# Threeno_Tx_Rev1B.net
KiCad netlist of a schematic drawn in EAGLE
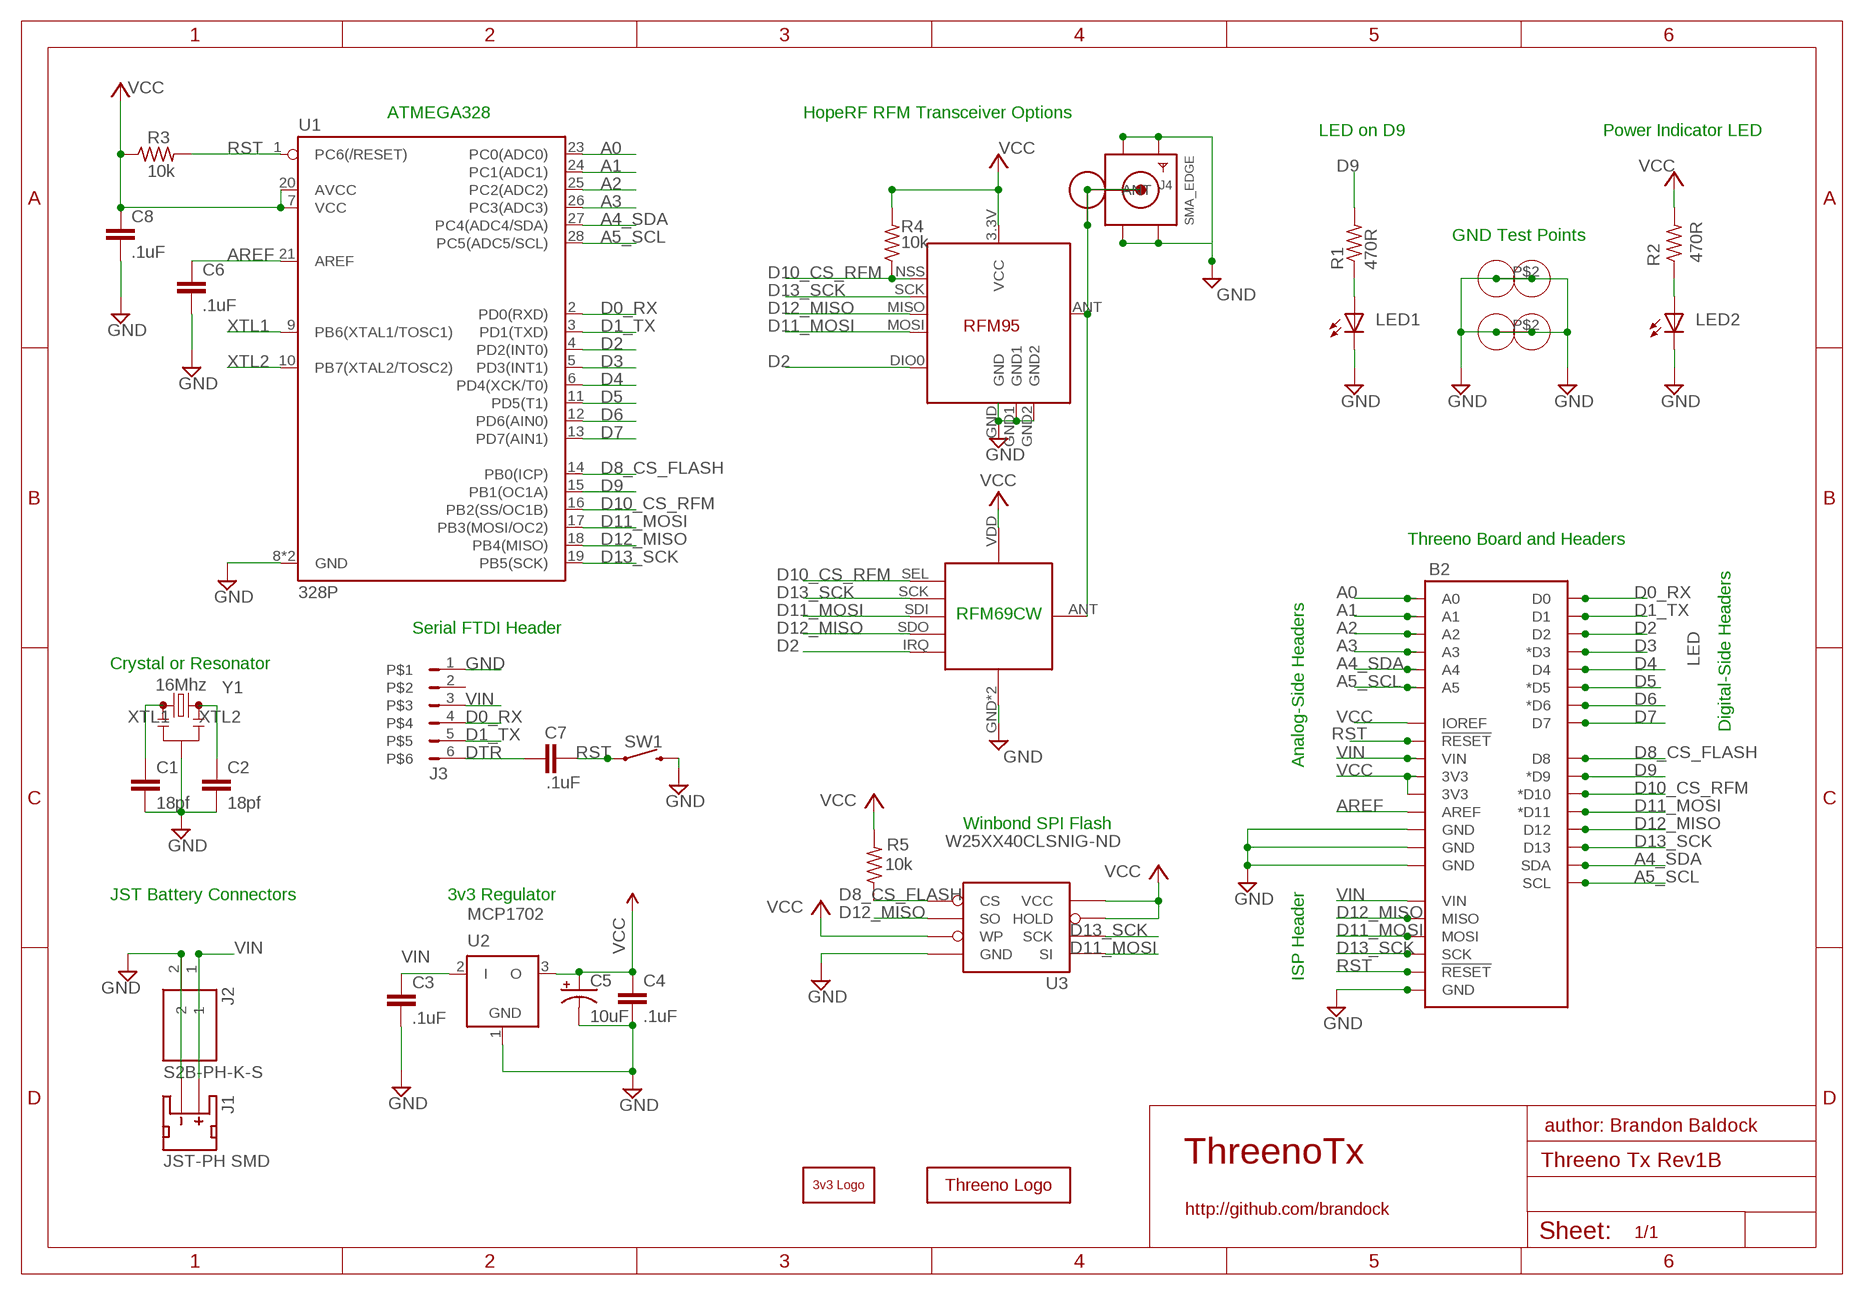
[diagram p0: schematic, sheet 1]

(export (version "E")
  (design (tool "Eeschema 10.0.6"))
  (components
    (comp (ref "B1")
      (value "3VTHREENO_BOTTOM_SILK")
      (footprint "eagle-import:3VTHREENO_BOTTOM_SILK")
      (libsource (lib "eagle-import") (part "3VTHREENO_BOTTOM_SILK"))
    )
    (comp (ref "B2")
      (value "THREENO_TX_BOARD3VTHREENO")
      (footprint "eagle-import:THREENO_TX_BOARD")
      (libsource (lib "eagle-import") (part "THREENO_TX_BOARD3VTHREENO"))
    )
    (comp (ref "B3")
      (value "3VTHREENO_LOGO")
      (footprint "eagle-import:3VTHREENO_LOGO")
      (libsource (lib "eagle-import") (part "3VTHREENO_LOGO"))
    )
    (comp (ref "C1")
      (value "18pf")
      (footprint "eagle-import:C025-024X044-NO-MIDDLE-SILK")
      (libsource (lib "eagle-import") (part "C-EU025-024X044-NO_MIDDLE_SILK"))
    )
    (comp (ref "C2")
      (value "18pf")
      (footprint "eagle-import:C025-024X044-NO-MIDDLE-SILK")
      (libsource (lib "eagle-import") (part "C-EU025-024X044-NO_MIDDLE_SILK"))
    )
    (comp (ref "C3")
      (value ".1uF")
      (footprint "eagle-import:C025-024X044-NO-MIDDLE-SILK")
      (libsource (lib "eagle-import") (part "C-EU025-024X044-NO_MIDDLE_SILK"))
    )
    (comp (ref "C4")
      (value ".1uF")
      (footprint "eagle-import:C025-024X044-NO-MIDDLE-SILK")
      (libsource (lib "eagle-import") (part "C-EU025-024X044-NO_MIDDLE_SILK"))
    )
    (comp (ref "C5")
      (value "10uF")
      (footprint "eagle-import:E1,8-4")
      (libsource (lib "eagle-import") (part "CPOL-USE1.8-4"))
    )
    (comp (ref "C6")
      (value ".1uF")
      (footprint "eagle-import:C025-024X044-NO-MIDDLE-SILK")
      (libsource (lib "eagle-import") (part "C-EU025-024X044-NO_MIDDLE_SILK"))
    )
    (comp (ref "C7")
      (value ".1uF")
      (footprint "eagle-import:C025-024X044-NO-MIDDLE-SILK")
      (libsource (lib "eagle-import") (part "C-EU025-024X044-NO_MIDDLE_SILK"))
    )
    (comp (ref "C8")
      (value ".1uF")
      (footprint "eagle-import:C025-024X044-NO-MIDDLE-SILK")
      (libsource (lib "eagle-import") (part "C-EU025-024X044-NO_MIDDLE_SILK"))
    )
    (comp (ref "J1")
      (value "JST-PH-SMD")
      (footprint "eagle-import:JST-2-SMD")
      (libsource (lib "eagle-import") (part "JST_2MM_MALE"))
    )
    (comp (ref "J2")
      (value "S2B-PH-K-S")
      (footprint "eagle-import:S2BPHKS")
      (libsource (lib "eagle-import") (part "S2B-PH-K-S"))
    )
    (comp (ref "J3")
      (value "FTDI")
      (footprint "eagle-import:FTDI_ROUND_HEADER_SILK")
      (libsource (lib "eagle-import") (part "FTDI"))
    )
    (comp (ref "J4")
      (value "SMA_EDGE")
      (footprint "eagle-import:SMA_EDGELAUNCH")
      (libsource (lib "eagle-import") (part "SMACONNECTOR_EDGE"))
    )
    (comp (ref "J5")
      (value "RFM12B_ANTENNA")
      (footprint "eagle-import:RFM12B-ANTENNA")
      (libsource (lib "eagle-import") (part "RFM12B_ANTENNA"))
    )
    (comp (ref "J6")
      (value "ALLIGATORCLIP-WIRELOOP")
      (footprint "eagle-import:ALLIGATORCLIP-WIRELOOP")
      (libsource (lib "eagle-import") (part "ALLIGATORCLIP-WIRELOOP"))
    )
    (comp (ref "J7")
      (value "ALLIGATORCLIP-WIRELOOP")
      (footprint "eagle-import:ALLIGATORCLIP-WIRELOOP")
      (libsource (lib "eagle-import") (part "ALLIGATORCLIP-WIRELOOP"))
    )
    (comp (ref "LED1")
      (value "LED")
      (footprint "eagle-import:LED3MM-BRANDOCK")
      (libsource (lib "eagle-import") (part "LED-BRANDOCK3MM"))
    )
    (comp (ref "LED2")
      (value "LED")
      (footprint "eagle-import:LED3MM-BRANDOCK")
      (libsource (lib "eagle-import") (part "LED-BRANDOCK3MM"))
    )
    (comp (ref "R1")
      (value "470R")
      (footprint "eagle-import:0204_7")
      (libsource (lib "eagle-import") (part "R-US_0204/7"))
    )
    (comp (ref "R2")
      (value "470R")
      (footprint "eagle-import:0204_7")
      (libsource (lib "eagle-import") (part "R-US_0204/7"))
    )
    (comp (ref "R3")
      (value "10k")
      (footprint "eagle-import:0204_7")
      (libsource (lib "eagle-import") (part "R-US_0204/7"))
    )
    (comp (ref "R4")
      (value "10k")
      (footprint "eagle-import:0204_7")
      (libsource (lib "eagle-import") (part "R-US_0204/7"))
    )
    (comp (ref "R5")
      (value "10k")
      (footprint "eagle-import:0204_7")
      (libsource (lib "eagle-import") (part "R-US_0204/7"))
    )
    (comp (ref "RF1")
      (value "RFM12B_MINPADS")
      (footprint "eagle-import:RFM12B-MINPADS")
      (libsource (lib "eagle-import") (part "RFM12B_MINPADS"))
    )
    (comp (ref "RF2")
      (value "RFM95LONGER")
      (footprint "eagle-import:RFM95_LONGER")
      (libsource (lib "eagle-import") (part "RFM95LONGER"))
    )
    (comp (ref "SW1")
      (value "MOMENTARY-SWITCH-SPST-PTH-6.0MM")
      (footprint "eagle-import:TACTILE_SWITCH_PTH_6.0MM")
      (libsource (lib "eagle-import") (part "MOMENTARY-SWITCH-SPST-PTH-6.0MM"))
    )
    (comp (ref "U1")
      (value "328P")
      (footprint "eagle-import:DIP28-OVALPADS")
      (libsource (lib "eagle-import") (part "ATMEGA328P_PDIP_DIL28"))
    )
    (comp (ref "U2")
      (value "JEELABS_MCP1702Z")
      (footprint "eagle-import:JEELABS_TO92")
      (fields (field (name "LDO") "MCP1702"))
      (libsource (lib "eagle-import") (part "JEELABS_MCP1702Z"))
    )
    (comp (ref "U3")
      (value "AT25F512BJEDEC_3.9MM")
      (footprint "eagle-import:SO08")
      (fields (field (name "FLASH_MEM") "W25XX40CLSNIG-ND"))
      (libsource (lib "eagle-import") (part "AT25F512BJEDEC_3.9MM"))
    )
    (comp (ref "Y1")
      (value "16Mhz")
      (footprint "eagle-import:HC49US-OR-RESONATOR")
      (libsource (lib "eagle-import") (part "CRYSTAL-OR-RESONATOR"))
    )
  )
  (nets
    (net (code "1") (name "/A0") (class "Default")
      (node (ref "B2") (pin "A0") (pinfunction "A0_A0") (pintype "bidirectional"))
      (node (ref "U1") (pin "23") (pinfunction "PC0(ADC0)_23") (pintype "bidirectional"))
    )
    (net (code "2") (name "/A1") (class "Default")
      (node (ref "B2") (pin "A1") (pinfunction "A1_A1") (pintype "bidirectional"))
      (node (ref "U1") (pin "24") (pinfunction "PC1(ADC1)_24") (pintype "bidirectional"))
    )
    (net (code "3") (name "/A2") (class "Default")
      (node (ref "B2") (pin "A2") (pinfunction "A2_A2") (pintype "bidirectional"))
      (node (ref "U1") (pin "25") (pinfunction "PC2(ADC2)_25") (pintype "bidirectional"))
    )
    (net (code "4") (name "/A3") (class "Default")
      (node (ref "B2") (pin "A3") (pinfunction "A3_A3") (pintype "bidirectional"))
      (node (ref "U1") (pin "26") (pinfunction "PC3(ADC3)_26") (pintype "bidirectional"))
    )
    (net (code "5") (name "/A4_SDA") (class "Default")
      (node (ref "B2") (pin "A4") (pinfunction "A4_A4") (pintype "bidirectional"))
      (node (ref "B2") (pin "SDA") (pinfunction "SDA_SDA") (pintype "bidirectional"))
      (node (ref "U1") (pin "27") (pinfunction "PC4(ADC4/SDA)_27") (pintype "bidirectional"))
    )
    (net (code "6") (name "/A5_SCL") (class "Default")
      (node (ref "B2") (pin "A5") (pinfunction "A5_A5") (pintype "bidirectional"))
      (node (ref "B2") (pin "SCL") (pinfunction "SCL_SCL") (pintype "bidirectional"))
      (node (ref "U1") (pin "28") (pinfunction "PC5(ADC5/SCL)_28") (pintype "bidirectional"))
    )
    (net (code "7") (name "/AREF") (class "Default")
      (node (ref "B2") (pin "AREF") (pinfunction "AREF_AREF") (pintype "bidirectional"))
      (node (ref "C6") (pin "1") (pinfunction "1_1") (pintype "passive"))
      (node (ref "U1") (pin "21") (pinfunction "AREF_21") (pintype "bidirectional"))
    )
    (net (code "8") (name "/D0_RX") (class "Default")
      (node (ref "B2") (pin "D0") (pinfunction "D0_D0") (pintype "bidirectional"))
      (node (ref "J3") (pin "4") (pinfunction "P$4_4") (pintype "bidirectional"))
      (node (ref "U1") (pin "2") (pinfunction "PD0(RXD)_2") (pintype "bidirectional"))
    )
    (net (code "9") (name "/D1_TX") (class "Default")
      (node (ref "B2") (pin "D1") (pinfunction "D1_D1") (pintype "bidirectional"))
      (node (ref "J3") (pin "5") (pinfunction "P$5_5") (pintype "bidirectional"))
      (node (ref "U1") (pin "3") (pinfunction "PD1(TXD)_3") (pintype "bidirectional"))
    )
    (net (code "10") (name "/D2") (class "Default")
      (node (ref "B2") (pin "D2") (pinfunction "D2_D2") (pintype "bidirectional"))
      (node (ref "RF1") (pin "IRQ") (pinfunction "IRQ_IRQ") (pintype "bidirectional"))
      (node (ref "RF2") (pin "DIO0") (pinfunction "DIO0_DIO0") (pintype "open_collector"))
      (node (ref "U1") (pin "4") (pinfunction "PD2(INT0)_4") (pintype "bidirectional"))
    )
    (net (code "11") (name "/D3") (class "Default")
      (node (ref "B2") (pin "D3") (pinfunction "*D3_D3") (pintype "bidirectional"))
      (node (ref "U1") (pin "5") (pinfunction "PD3(INT1)_5") (pintype "bidirectional"))
    )
    (net (code "12") (name "/D4") (class "Default")
      (node (ref "B2") (pin "D4") (pinfunction "D4_D4") (pintype "bidirectional"))
      (node (ref "U1") (pin "6") (pinfunction "PD4(XCK/T0)_6") (pintype "bidirectional"))
    )
    (net (code "13") (name "/D5") (class "Default")
      (node (ref "B2") (pin "D5") (pinfunction "*D5_D5") (pintype "bidirectional"))
      (node (ref "U1") (pin "11") (pinfunction "PD5(T1)_11") (pintype "bidirectional"))
    )
    (net (code "14") (name "/D6") (class "Default")
      (node (ref "B2") (pin "D6") (pinfunction "*D6_D6") (pintype "bidirectional"))
      (node (ref "U1") (pin "12") (pinfunction "PD6(AIN0)_12") (pintype "bidirectional"))
    )
    (net (code "15") (name "/D7") (class "Default")
      (node (ref "B2") (pin "D7") (pinfunction "D7_D7") (pintype "bidirectional"))
      (node (ref "U1") (pin "13") (pinfunction "PD7(AIN1)_13") (pintype "bidirectional"))
    )
    (net (code "16") (name "/D8_CS_FLASH") (class "Default")
      (node (ref "B2") (pin "D8") (pinfunction "D8_D8") (pintype "bidirectional"))
      (node (ref "R5") (pin "1") (pinfunction "1_1") (pintype "passive"))
      (node (ref "U1") (pin "14") (pinfunction "PB0(ICP)_14") (pintype "bidirectional"))
      (node (ref "U3") (pin "1_CS") (pinfunction "CS_1_CS") (pintype "bidirectional"))
    )
    (net (code "17") (name "/D9") (class "Default")
      (node (ref "B2") (pin "D9") (pinfunction "*D9_D9") (pintype "bidirectional"))
      (node (ref "R1") (pin "2") (pinfunction "2_2") (pintype "passive"))
      (node (ref "U1") (pin "15") (pinfunction "PB1(OC1A)_15") (pintype "bidirectional"))
    )
    (net (code "18") (name "/D10_CS_RFM") (class "Default")
      (node (ref "B2") (pin "D10") (pinfunction "*D10_D10") (pintype "bidirectional"))
      (node (ref "R4") (pin "1") (pinfunction "1_1") (pintype "passive"))
      (node (ref "RF1") (pin "SEL") (pinfunction "SEL_SEL") (pintype "bidirectional"))
      (node (ref "RF2") (pin "NSS") (pinfunction "SEL_NSS") (pintype "input"))
      (node (ref "U1") (pin "16") (pinfunction "PB2(SS/OC1B)_16") (pintype "bidirectional"))
    )
    (net (code "19") (name "/D11_MOSI") (class "Default")
      (node (ref "B2") (pin "D11") (pinfunction "*D11_D11") (pintype "bidirectional"))
      (node (ref "B2") (pin "MOSI@ICSP") (pinfunction "MOSI_MOSI@ICSP") (pintype "bidirectional"))
      (node (ref "RF1") (pin "SDI") (pinfunction "SDI/MOSI_SDI") (pintype "bidirectional"))
      (node (ref "RF2") (pin "MOSI") (pinfunction "MOSI_MOSI") (pintype "output"))
      (node (ref "U1") (pin "17") (pinfunction "PB3(MOSI/OC2)_17") (pintype "bidirectional"))
      (node (ref "U3") (pin "5_SI") (pinfunction "SI_5_SI") (pintype "bidirectional"))
    )
    (net (code "20") (name "/D12_MISO") (class "Default")
      (node (ref "B2") (pin "D12") (pinfunction "D12_D12") (pintype "bidirectional"))
      (node (ref "B2") (pin "MISO@ICSP") (pinfunction "MISO_MISO@ICSP") (pintype "bidirectional"))
      (node (ref "RF1") (pin "SDO") (pinfunction "SDO/MISO_SDO") (pintype "bidirectional"))
      (node (ref "RF2") (pin "MISO") (pinfunction "MISO_MISO") (pintype "input"))
      (node (ref "U1") (pin "18") (pinfunction "PB4(MISO)_18") (pintype "bidirectional"))
      (node (ref "U3") (pin "2_SO") (pinfunction "SO_2_SO") (pintype "bidirectional"))
    )
    (net (code "21") (name "/D13_SCK") (class "Default")
      (node (ref "B2") (pin "D13") (pinfunction "D13_D13") (pintype "bidirectional"))
      (node (ref "B2") (pin "SCK@ICSP") (pinfunction "SCK_SCK@ICSP") (pintype "bidirectional"))
      (node (ref "RF1") (pin "SCK") (pinfunction "SCK_SCK") (pintype "bidirectional"))
      (node (ref "RF2") (pin "SCK") (pinfunction "SCK_SCK") (pintype "input"))
      (node (ref "U1") (pin "19") (pinfunction "PB5(SCK)_19") (pintype "bidirectional"))
      (node (ref "U3") (pin "6_SCK") (pinfunction "SCK_6_SCK") (pintype "bidirectional"))
    )
    (net (code "22") (name "/DTR") (class "Default")
      (node (ref "C7") (pin "1") (pinfunction "1_1") (pintype "passive"))
      (node (ref "J3") (pin "6") (pinfunction "P$6_6") (pintype "bidirectional"))
    )
    (net (code "23") (name "/RST") (class "Default")
      (node (ref "B2") (pin "RESET@1") (pinfunction "~{RESET}_RESET@1") (pintype "bidirectional"))
      (node (ref "B2") (pin "RESET@ICSP") (pinfunction "~{RESET}_RESET@ICSP") (pintype "bidirectional"))
      (node (ref "C7") (pin "2") (pinfunction "2_2") (pintype "passive"))
      (node (ref "R3") (pin "2") (pinfunction "2_2") (pintype "passive"))
      (node (ref "SW1") (pin "1") (pinfunction "1_1") (pintype "passive"))
      (node (ref "U1") (pin "1") (pinfunction "PC6(/RESET)_1") (pintype "bidirectional"))
    )
    (net (code "24") (name "/VIN") (class "Default")
      (node (ref "B2") (pin "VIN") (pinfunction "VIN_VIN") (pintype "bidirectional"))
      (node (ref "B2") (pin "VIN@ICSP") (pinfunction "VIN_VIN@ICSP") (pintype "bidirectional"))
      (node (ref "C3") (pin "1") (pinfunction "1_1") (pintype "passive"))
      (node (ref "J1") (pin "2") (pinfunction "+_2") (pintype "bidirectional"))
      (node (ref "J2") (pin "1") (pinfunction "1_1") (pintype "bidirectional"))
      (node (ref "J3") (pin "3") (pinfunction "P$3_3") (pintype "bidirectional"))
      (node (ref "U2") (pin "2") (pinfunction "I_2") (pintype "input"))
    )
    (net (code "25") (name "/XTL1") (class "Default")
      (node (ref "C1") (pin "1") (pinfunction "1_1") (pintype "passive"))
      (node (ref "U1") (pin "9") (pinfunction "PB6(XTAL1/TOSC1)_9") (pintype "bidirectional"))
      (node (ref "Y1") (pin "1") (pinfunction "1_1") (pintype "passive"))
    )
    (net (code "26") (name "/XTL2") (class "Default")
      (node (ref "C2") (pin "1") (pinfunction "1_1") (pintype "passive"))
      (node (ref "U1") (pin "10") (pinfunction "PB7(XTAL2/TOSC2)_10") (pintype "bidirectional"))
      (node (ref "Y1") (pin "3") (pinfunction "3_3") (pintype "passive"))
    )
    (net (code "27") (name "3.3V") (class "Default")
      (node (ref "B2") (pin "3.3V") (pinfunction "3V3_3.3V") (pintype "bidirectional"))
      (node (ref "B2") (pin "3.3V@2") (pinfunction "3V3_3.3V@2") (pintype "bidirectional"))
      (node (ref "B2") (pin "IOREF") (pinfunction "IOREF_IOREF") (pintype "bidirectional"))
      (node (ref "C4") (pin "1") (pinfunction "1_1") (pintype "passive"))
      (node (ref "C5") (pin "+") (pinfunction "+_+") (pintype "passive"))
      (node (ref "C8") (pin "1") (pinfunction "1_1") (pintype "passive"))
      (node (ref "R2") (pin "2") (pinfunction "2_2") (pintype "passive"))
      (node (ref "R3") (pin "1") (pinfunction "1_1") (pintype "passive"))
      (node (ref "R4") (pin "2") (pinfunction "2_2") (pintype "passive"))
      (node (ref "R5") (pin "2") (pinfunction "2_2") (pintype "passive"))
      (node (ref "RF1") (pin "VDD") (pinfunction "VDD_VDD") (pintype "bidirectional"))
      (node (ref "RF2") (pin "3.3V") (pinfunction "VCC_3.3V") (pintype "power_in"))
      (node (ref "U1") (pin "20") (pinfunction "AVCC_20") (pintype "bidirectional"))
      (node (ref "U1") (pin "7") (pinfunction "VCC_7") (pintype "bidirectional"))
      (node (ref "U2") (pin "3") (pinfunction "O_3") (pintype "input"))
      (node (ref "U3") (pin "3_WP") (pinfunction "WP_3_WP") (pintype "bidirectional"))
      (node (ref "U3") (pin "7_HOLD") (pinfunction "HOLD_7_HOLD") (pintype "bidirectional"))
      (node (ref "U3") (pin "8_VCC") (pinfunction "VCC_8_VCC") (pintype "bidirectional"))
    )
    (net (code "28") (name "GND") (class "Default")
      (node (ref "B2") (pin "GND@1") (pinfunction "GND_GND@1") (pintype "bidirectional"))
      (node (ref "B2") (pin "GND@2") (pinfunction "GND_GND@2") (pintype "bidirectional"))
      (node (ref "B2") (pin "GND@3") (pinfunction "GND_GND@3") (pintype "bidirectional"))
      (node (ref "B2") (pin "GND@ICSP") (pinfunction "GND_GND@ICSP") (pintype "bidirectional"))
      (node (ref "C1") (pin "2") (pinfunction "2_2") (pintype "passive"))
      (node (ref "C2") (pin "2") (pinfunction "2_2") (pintype "passive"))
      (node (ref "C3") (pin "2") (pinfunction "2_2") (pintype "passive"))
      (node (ref "C4") (pin "2") (pinfunction "2_2") (pintype "passive"))
      (node (ref "C5") (pin "-") (pinfunction "-_-") (pintype "passive"))
      (node (ref "C6") (pin "2") (pinfunction "2_2") (pintype "passive"))
      (node (ref "C8") (pin "2") (pinfunction "2_2") (pintype "passive"))
      (node (ref "J1") (pin "1") (pinfunction "-_1") (pintype "bidirectional"))
      (node (ref "J2") (pin "2") (pinfunction "2_2") (pintype "bidirectional"))
      (node (ref "J3") (pin "1") (pinfunction "P$1_1") (pintype "bidirectional"))
      (node (ref "J4") (pin "GND@1") (pinfunction "GND4_GND@1") (pintype "power_in"))
      (node (ref "J4") (pin "GND@2") (pinfunction "GND3_GND@2") (pintype "power_in"))
      (node (ref "J4") (pin "GND@3") (pinfunction "GND2_GND@3") (pintype "power_in"))
      (node (ref "J4") (pin "GND@4") (pinfunction "GND1_GND@4") (pintype "power_in"))
      (node (ref "J6") (pin "P$1") (pinfunction "P$1_P$1") (pintype "bidirectional"))
      (node (ref "J6") (pin "P$2") (pinfunction "P$2_P$2") (pintype "bidirectional"))
      (node (ref "J7") (pin "P$1") (pinfunction "P$1_P$1") (pintype "bidirectional"))
      (node (ref "J7") (pin "P$2") (pinfunction "P$2_P$2") (pintype "bidirectional"))
      (node (ref "LED1") (pin "K") (pinfunction "C_K") (pintype "passive"))
      (node (ref "LED2") (pin "K") (pinfunction "C_K") (pintype "passive"))
      (node (ref "RF1") (pin "GND") (pinfunction "GND_GND") (pintype "bidirectional"))
      (node (ref "RF1") (pin "GND2") (pinfunction "GND_GND2") (pintype "bidirectional"))
      (node (ref "RF2") (pin "GND") (pinfunction "GND_GND") (pintype "power_in"))
      (node (ref "RF2") (pin "GND1") (pinfunction "GND1_GND1") (pintype "power_in"))
      (node (ref "RF2") (pin "GND2") (pinfunction "GND2_GND2") (pintype "power_in"))
      (node (ref "SW1") (pin "3") (pinfunction "2_3") (pintype "passive"))
      (node (ref "U1") (pin "22") (pinfunction "GND_22") (pintype "bidirectional"))
      (node (ref "U1") (pin "8") (pinfunction "GND_8") (pintype "bidirectional"))
      (node (ref "U2") (pin "1") (pinfunction "GND_1") (pintype "power_in"))
      (node (ref "U3") (pin "4_GND") (pinfunction "GND_4_GND") (pintype "bidirectional"))
      (node (ref "Y1") (pin "2") (pinfunction "2_2") (pintype "passive"))
    )
    (net (code "29") (name "Net-(J4-ANT)") (class "Default")
      (node (ref "J4") (pin "P") (pinfunction "ANT_P") (pintype "bidirectional"))
      (node (ref "J5") (pin "P$1") (pinfunction "1_P$1") (pintype "bidirectional"))
      (node (ref "RF1") (pin "ANT") (pinfunction "ANT_ANT") (pintype "bidirectional"))
      (node (ref "RF2") (pin "ANT") (pinfunction "ANT_ANT") (pintype "passive"))
    )
    (net (code "30") (name "Net-(LED1-PadA)") (class "Default")
      (node (ref "LED1") (pin "A") (pinfunction "A_A") (pintype "passive"))
      (node (ref "R1") (pin "1") (pinfunction "1_1") (pintype "passive"))
    )
    (net (code "31") (name "Net-(LED2-PadA)") (class "Default")
      (node (ref "LED2") (pin "A") (pinfunction "A_A") (pintype "passive"))
      (node (ref "R2") (pin "1") (pinfunction "1_1") (pintype "passive"))
    )
    (net (code "32") (name "unconnected-(J1-PAD1-PadNC1)") (class "Default")
      (node (ref "J1") (pin "NC1") (pinfunction "PAD1_NC1") (pintype "bidirectional"))
    )
    (net (code "33") (name "unconnected-(J1-PAD2-PadNC2)") (class "Default")
      (node (ref "J1") (pin "NC2") (pinfunction "PAD2_NC2") (pintype "bidirectional"))
    )
    (net (code "34") (name "unconnected-(J3-P$2-Pad2)") (class "Default")
      (node (ref "J3") (pin "2") (pinfunction "P$2_2") (pintype "bidirectional"))
    )
  )
)
